# bit-shifter.net
KiCad netlist of a schematic drawn in EAGLE
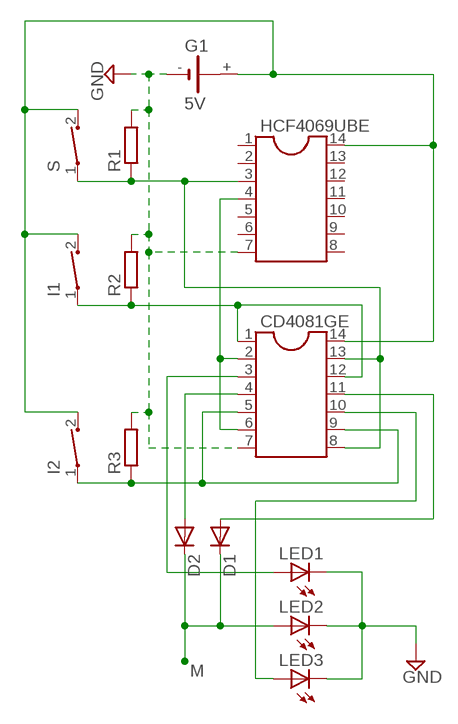
[diagram p0: schematic, sheet 1]

(export (version "E")
  (design (tool "Eeschema 10.0.6"))
  (components
    (comp (ref "CD4081GE")
      (value "DIL14")
      (footprint "eagle-import:DIL14")
      (libsource (lib "eagle-import") (part "DIL14"))
    )
    (comp (ref "D1")
      (value "1N4446")
      (footprint "eagle-import:DO35-10")
      (libsource (lib "eagle-import") (part "1N4446"))
    )
    (comp (ref "D2")
      (value "1N4446")
      (footprint "eagle-import:DO35-10")
      (libsource (lib "eagle-import") (part "1N4446"))
    )
    (comp (ref "G1")
      (value "5V")
      (footprint "eagle-import:1V60R")
      (libsource (lib "eagle-import") (part "1V60R"))
    )
    (comp (ref "HCF4069UBE")
      (value "DIL14")
      (footprint "eagle-import:DIL14")
      (libsource (lib "eagle-import") (part "DIL14"))
    )
    (comp (ref "I1")
      (value "CT10-XXXX-A2")
      (footprint "eagle-import:CT10-XXXX-A2")
      (libsource (lib "eagle-import") (part "CT10-XXXX-A2"))
    )
    (comp (ref "I2")
      (value "CT10-XXXX-A2")
      (footprint "eagle-import:CT10-XXXX-A2")
      (libsource (lib "eagle-import") (part "CT10-XXXX-A2"))
    )
    (comp (ref "LED1")
      (value "LAP4-BOTTOM")
      (footprint "eagle-import:P47F-BOTTOM")
      (libsource (lib "eagle-import") (part "P4-BOTTOMLA"))
    )
    (comp (ref "LED2")
      (value "LAP4-BOTTOM")
      (footprint "eagle-import:P47F-BOTTOM")
      (libsource (lib "eagle-import") (part "P4-BOTTOMLA"))
    )
    (comp (ref "LED3")
      (value "LAP4-BOTTOM")
      (footprint "eagle-import:P47F-BOTTOM")
      (libsource (lib "eagle-import") (part "P4-BOTTOMLA"))
    )
    (comp (ref "R1")
      (value "R-EU_0204/2V")
      (footprint "eagle-import:0204V")
      (libsource (lib "eagle-import") (part "R-EU_0204/2V"))
    )
    (comp (ref "R2")
      (value "R-EU_0204/2V")
      (footprint "eagle-import:0204V")
      (libsource (lib "eagle-import") (part "R-EU_0204/2V"))
    )
    (comp (ref "R3")
      (value "R-EU_0204/2V")
      (footprint "eagle-import:0204V")
      (libsource (lib "eagle-import") (part "R-EU_0204/2V"))
    )
    (comp (ref "S")
      (value "CT10-XXXX-A2")
      (footprint "eagle-import:CT10-XXXX-A2")
      (libsource (lib "eagle-import") (part "CT10-XXXX-A2"))
    )
  )
  (nets
    (net (code "1") (name "GND") (class "Default")
      (node (ref "CD4081GE") (pin "7") (pinfunction "7_7") (pintype "passive"))
      (node (ref "G1") (pin "-") (pinfunction "-_-") (pintype "passive"))
      (node (ref "HCF4069UBE") (pin "7") (pinfunction "7_7") (pintype "passive"))
      (node (ref "LED1") (pin "C") (pinfunction "C_C") (pintype "passive"))
      (node (ref "LED2") (pin "C") (pinfunction "C_C") (pintype "passive"))
      (node (ref "LED3") (pin "C") (pinfunction "C_C") (pintype "passive"))
      (node (ref "R1") (pin "2") (pinfunction "2_2") (pintype "passive"))
      (node (ref "R2") (pin "2") (pinfunction "2_2") (pintype "passive"))
      (node (ref "R3") (pin "2") (pinfunction "2_2") (pintype "passive"))
    )
    (net (code "2") (name "Net-(CD4081GE-Pad1)") (class "Default")
      (node (ref "CD4081GE") (pin "1") (pinfunction "1_1") (pintype "passive"))
      (node (ref "CD4081GE") (pin "12") (pinfunction "12_12") (pintype "passive"))
      (node (ref "I1") (pin "1") (pinfunction "1_1") (pintype "passive"))
      (node (ref "R2") (pin "1") (pinfunction "1_1") (pintype "passive"))
    )
    (net (code "3") (name "Net-(CD4081GE-Pad2)") (class "Default")
      (node (ref "CD4081GE") (pin "2") (pinfunction "2_2") (pintype "passive"))
      (node (ref "CD4081GE") (pin "6") (pinfunction "6_6") (pintype "passive"))
      (node (ref "HCF4069UBE") (pin "4") (pinfunction "4_4") (pintype "passive"))
    )
    (net (code "4") (name "Net-(CD4081GE-Pad3)") (class "Default")
      (node (ref "CD4081GE") (pin "3") (pinfunction "3_3") (pintype "passive"))
      (node (ref "LED1") (pin "A") (pinfunction "A_A") (pintype "passive"))
    )
    (net (code "5") (name "Net-(CD4081GE-Pad4)") (class "Default")
      (node (ref "CD4081GE") (pin "4") (pinfunction "4_4") (pintype "passive"))
      (node (ref "D2") (pin "A") (pinfunction "A_A") (pintype "passive"))
    )
    (net (code "6") (name "Net-(CD4081GE-Pad5)") (class "Default")
      (node (ref "CD4081GE") (pin "5") (pinfunction "5_5") (pintype "passive"))
      (node (ref "CD4081GE") (pin "9") (pinfunction "9_9") (pintype "passive"))
      (node (ref "I2") (pin "1") (pinfunction "1_1") (pintype "passive"))
      (node (ref "R3") (pin "1") (pinfunction "1_1") (pintype "passive"))
    )
    (net (code "7") (name "Net-(CD4081GE-Pad10)") (class "Default")
      (node (ref "CD4081GE") (pin "10") (pinfunction "10_10") (pintype "passive"))
      (node (ref "LED3") (pin "A") (pinfunction "A_A") (pintype "passive"))
    )
    (net (code "8") (name "Net-(CD4081GE-Pad11)") (class "Default")
      (node (ref "CD4081GE") (pin "11") (pinfunction "11_11") (pintype "passive"))
      (node (ref "D1") (pin "A") (pinfunction "A_A") (pintype "passive"))
    )
    (net (code "9") (name "Net-(CD4081GE-Pad13)") (class "Default")
      (node (ref "CD4081GE") (pin "13") (pinfunction "13_13") (pintype "passive"))
      (node (ref "CD4081GE") (pin "8") (pinfunction "8_8") (pintype "passive"))
      (node (ref "HCF4069UBE") (pin "3") (pinfunction "3_3") (pintype "passive"))
      (node (ref "R1") (pin "1") (pinfunction "1_1") (pintype "passive"))
      (node (ref "S") (pin "1") (pinfunction "1_1") (pintype "passive"))
    )
    (net (code "10") (name "Net-(CD4081GE-Pad14)") (class "Default")
      (node (ref "CD4081GE") (pin "14") (pinfunction "14_14") (pintype "passive"))
      (node (ref "G1") (pin "+") (pinfunction "+_+") (pintype "passive"))
      (node (ref "HCF4069UBE") (pin "14") (pinfunction "14_14") (pintype "passive"))
      (node (ref "I1") (pin "2") (pinfunction "2_2") (pintype "passive"))
      (node (ref "I2") (pin "2") (pinfunction "2_2") (pintype "passive"))
      (node (ref "S") (pin "2") (pinfunction "2_2") (pintype "passive"))
    )
    (net (code "11") (name "Net-(D1-PadC)") (class "Default")
      (node (ref "D1") (pin "C") (pinfunction "C_C") (pintype "passive"))
      (node (ref "D2") (pin "C") (pinfunction "C_C") (pintype "passive"))
      (node (ref "LED2") (pin "A") (pinfunction "A_A") (pintype "passive"))
    )
    (net (code "12") (name "unconnected-(G1-+-Pad+@1)") (class "Default")
      (node (ref "G1") (pin "+@1") (pinfunction "+_+@1") (pintype "passive"))
    )
    (net (code "13") (name "unconnected-(HCF4069UBE-Pad1)") (class "Default")
      (node (ref "HCF4069UBE") (pin "1") (pinfunction "1_1") (pintype "passive"))
    )
    (net (code "14") (name "unconnected-(HCF4069UBE-Pad2)") (class "Default")
      (node (ref "HCF4069UBE") (pin "2") (pinfunction "2_2") (pintype "passive"))
    )
    (net (code "15") (name "unconnected-(HCF4069UBE-Pad5)") (class "Default")
      (node (ref "HCF4069UBE") (pin "5") (pinfunction "5_5") (pintype "passive"))
    )
    (net (code "16") (name "unconnected-(HCF4069UBE-Pad6)") (class "Default")
      (node (ref "HCF4069UBE") (pin "6") (pinfunction "6_6") (pintype "passive"))
    )
    (net (code "17") (name "unconnected-(HCF4069UBE-Pad8)") (class "Default")
      (node (ref "HCF4069UBE") (pin "8") (pinfunction "8_8") (pintype "passive"))
    )
    (net (code "18") (name "unconnected-(HCF4069UBE-Pad9)") (class "Default")
      (node (ref "HCF4069UBE") (pin "9") (pinfunction "9_9") (pintype "passive"))
    )
    (net (code "19") (name "unconnected-(HCF4069UBE-Pad10)") (class "Default")
      (node (ref "HCF4069UBE") (pin "10") (pinfunction "10_10") (pintype "passive"))
    )
    (net (code "20") (name "unconnected-(HCF4069UBE-Pad11)") (class "Default")
      (node (ref "HCF4069UBE") (pin "11") (pinfunction "11_11") (pintype "passive"))
    )
    (net (code "21") (name "unconnected-(HCF4069UBE-Pad12)") (class "Default")
      (node (ref "HCF4069UBE") (pin "12") (pinfunction "12_12") (pintype "passive"))
    )
    (net (code "22") (name "unconnected-(HCF4069UBE-Pad13)") (class "Default")
      (node (ref "HCF4069UBE") (pin "13") (pinfunction "13_13") (pintype "passive"))
    )
  )
)
